# 1-Schematic_light_panel.net
KiCad netlist of a schematic drawn in EasyEDA
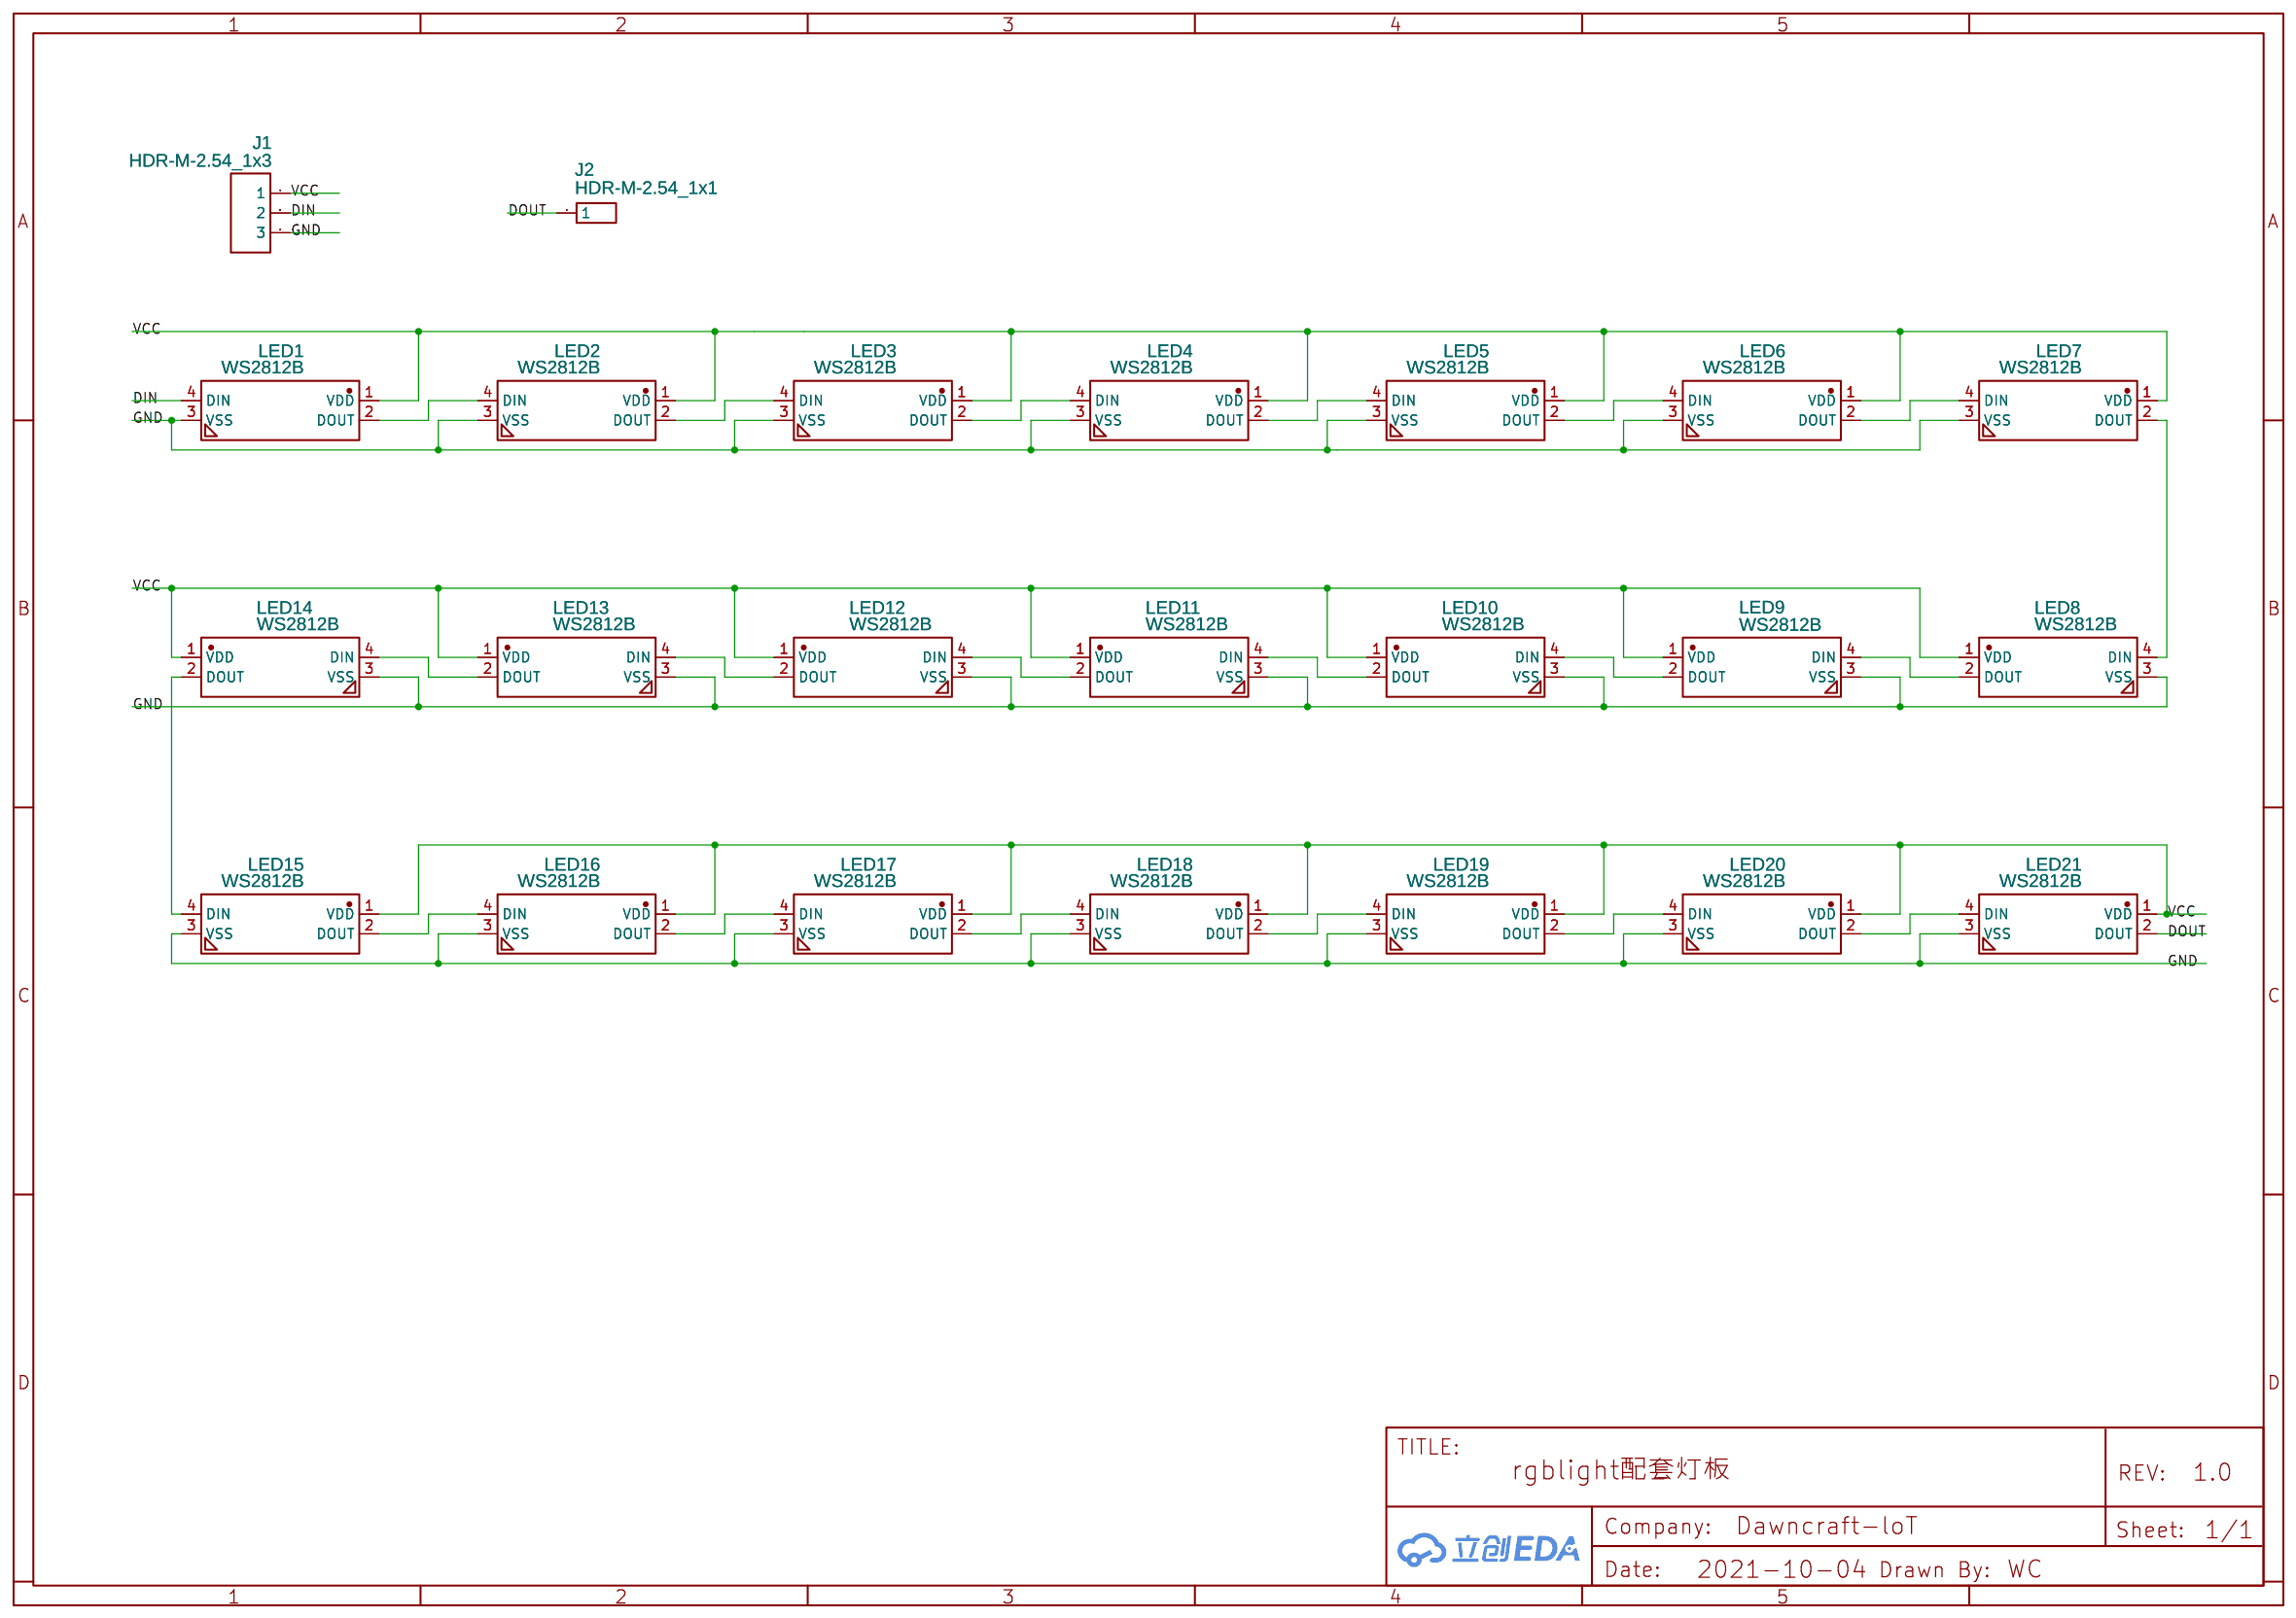
[diagram p0: schematic sheet]

(export (version "E")
  (design (tool "Eeschema 10.0.6"))
  (components
    (comp (ref "J1")
      (value "HDR-M-2.54_1x3")
      (fields (field (name "BOM_Supplier Part") "C180248"))
      (libsource (lib "") (part "HDR-M-2.54_1x3"))
    )
    (comp (ref "J2")
      (value "HDR-M-2.54_1x1")
      (fields (field (name "BOM_Supplier Part") "C81276"))
      (libsource (lib "") (part "HDR-M-2.54_1x1"))
    )
    (comp (ref "LED1")
      (value "WS2812B")
      (fields (field (name "BOM_Supplier Part") "C114585"))
      (libsource (lib "") (part "WS2812B"))
    )
    (comp (ref "LED2")
      (value "WS2812B")
      (fields (field (name "BOM_Supplier Part") "C114585"))
      (libsource (lib "") (part "WS2812B"))
    )
    (comp (ref "LED3")
      (value "WS2812B")
      (fields (field (name "BOM_Supplier Part") "C114585"))
      (libsource (lib "") (part "WS2812B"))
    )
    (comp (ref "LED4")
      (value "WS2812B")
      (fields (field (name "BOM_Supplier Part") "C114585"))
      (libsource (lib "") (part "WS2812B"))
    )
    (comp (ref "LED5")
      (value "WS2812B")
      (fields (field (name "BOM_Supplier Part") "C114585"))
      (libsource (lib "") (part "WS2812B"))
    )
    (comp (ref "LED6")
      (value "WS2812B")
      (fields (field (name "BOM_Supplier Part") "C114585"))
      (libsource (lib "") (part "WS2812B"))
    )
    (comp (ref "LED7")
      (value "WS2812B")
      (fields (field (name "BOM_Supplier Part") "C114585"))
      (libsource (lib "") (part "WS2812B"))
    )
    (comp (ref "LED8")
      (value "WS2812B")
      (fields (field (name "BOM_Supplier Part") "C114585"))
      (libsource (lib "") (part "WS2812B_1"))
    )
    (comp (ref "LED9")
      (value "WS2812B")
      (fields (field (name "BOM_Supplier Part") "C114585"))
      (libsource (lib "") (part "WS2812B_1"))
    )
    (comp (ref "LED10")
      (value "WS2812B")
      (fields (field (name "BOM_Supplier Part") "C114585"))
      (libsource (lib "") (part "WS2812B_1"))
    )
    (comp (ref "LED11")
      (value "WS2812B")
      (fields (field (name "BOM_Supplier Part") "C114585"))
      (libsource (lib "") (part "WS2812B_1"))
    )
    (comp (ref "LED12")
      (value "WS2812B")
      (fields (field (name "BOM_Supplier Part") "C114585"))
      (libsource (lib "") (part "WS2812B_1"))
    )
    (comp (ref "LED13")
      (value "WS2812B")
      (fields (field (name "BOM_Supplier Part") "C114585"))
      (libsource (lib "") (part "WS2812B_1"))
    )
    (comp (ref "LED14")
      (value "WS2812B")
      (fields (field (name "BOM_Supplier Part") "C114585"))
      (libsource (lib "") (part "WS2812B_1"))
    )
    (comp (ref "LED15")
      (value "WS2812B")
      (fields (field (name "BOM_Supplier Part") "C114585"))
      (libsource (lib "") (part "WS2812B"))
    )
    (comp (ref "LED16")
      (value "WS2812B")
      (fields (field (name "BOM_Supplier Part") "C114585"))
      (libsource (lib "") (part "WS2812B"))
    )
    (comp (ref "LED17")
      (value "WS2812B")
      (fields (field (name "BOM_Supplier Part") "C114585"))
      (libsource (lib "") (part "WS2812B"))
    )
    (comp (ref "LED18")
      (value "WS2812B")
      (fields (field (name "BOM_Supplier Part") "C114585"))
      (libsource (lib "") (part "WS2812B"))
    )
    (comp (ref "LED19")
      (value "WS2812B")
      (fields (field (name "BOM_Supplier Part") "C114585"))
      (libsource (lib "") (part "WS2812B"))
    )
    (comp (ref "LED20")
      (value "WS2812B")
      (fields (field (name "BOM_Supplier Part") "C114585"))
      (libsource (lib "") (part "WS2812B"))
    )
    (comp (ref "LED21")
      (value "WS2812B")
      (fields (field (name "BOM_Supplier Part") "C114585"))
      (libsource (lib "") (part "WS2812B"))
    )
  )
  (nets
    (net (code "1") (name "/DIN") (class "Default")
      (node (ref "J1") (pin "2") (pinfunction "2_2") (pintype "input"))
      (node (ref "LED1") (pin "4") (pinfunction "DIN_4") (pintype "unspecified"))
    )
    (net (code "2") (name "/DOUT") (class "Default")
      (node (ref "J2") (pin "1") (pinfunction "1_1") (pintype "input"))
      (node (ref "LED21") (pin "2") (pinfunction "DOUT_2") (pintype "unspecified"))
    )
    (net (code "3") (name "/GND") (class "Default")
      (node (ref "J1") (pin "3") (pinfunction "3_3") (pintype "input"))
      (node (ref "LED1") (pin "3") (pinfunction "VSS_3") (pintype "unspecified"))
      (node (ref "LED10") (pin "3") (pinfunction "VSS_3") (pintype "unspecified"))
      (node (ref "LED11") (pin "3") (pinfunction "VSS_3") (pintype "unspecified"))
      (node (ref "LED12") (pin "3") (pinfunction "VSS_3") (pintype "unspecified"))
      (node (ref "LED13") (pin "3") (pinfunction "VSS_3") (pintype "unspecified"))
      (node (ref "LED14") (pin "3") (pinfunction "VSS_3") (pintype "unspecified"))
      (node (ref "LED15") (pin "3") (pinfunction "VSS_3") (pintype "unspecified"))
      (node (ref "LED16") (pin "3") (pinfunction "VSS_3") (pintype "unspecified"))
      (node (ref "LED17") (pin "3") (pinfunction "VSS_3") (pintype "unspecified"))
      (node (ref "LED18") (pin "3") (pinfunction "VSS_3") (pintype "unspecified"))
      (node (ref "LED19") (pin "3") (pinfunction "VSS_3") (pintype "unspecified"))
      (node (ref "LED2") (pin "3") (pinfunction "VSS_3") (pintype "unspecified"))
      (node (ref "LED20") (pin "3") (pinfunction "VSS_3") (pintype "unspecified"))
      (node (ref "LED21") (pin "3") (pinfunction "VSS_3") (pintype "unspecified"))
      (node (ref "LED3") (pin "3") (pinfunction "VSS_3") (pintype "unspecified"))
      (node (ref "LED4") (pin "3") (pinfunction "VSS_3") (pintype "unspecified"))
      (node (ref "LED5") (pin "3") (pinfunction "VSS_3") (pintype "unspecified"))
      (node (ref "LED6") (pin "3") (pinfunction "VSS_3") (pintype "unspecified"))
      (node (ref "LED7") (pin "3") (pinfunction "VSS_3") (pintype "unspecified"))
      (node (ref "LED8") (pin "3") (pinfunction "VSS_3") (pintype "unspecified"))
      (node (ref "LED9") (pin "3") (pinfunction "VSS_3") (pintype "unspecified"))
    )
    (net (code "4") (name "/VCC") (class "Default")
      (node (ref "J1") (pin "1") (pinfunction "1_1") (pintype "input"))
      (node (ref "LED1") (pin "1") (pinfunction "VDD_1") (pintype "unspecified"))
      (node (ref "LED10") (pin "1") (pinfunction "VDD_1") (pintype "unspecified"))
      (node (ref "LED11") (pin "1") (pinfunction "VDD_1") (pintype "unspecified"))
      (node (ref "LED12") (pin "1") (pinfunction "VDD_1") (pintype "unspecified"))
      (node (ref "LED13") (pin "1") (pinfunction "VDD_1") (pintype "unspecified"))
      (node (ref "LED14") (pin "1") (pinfunction "VDD_1") (pintype "unspecified"))
      (node (ref "LED15") (pin "1") (pinfunction "VDD_1") (pintype "unspecified"))
      (node (ref "LED16") (pin "1") (pinfunction "VDD_1") (pintype "unspecified"))
      (node (ref "LED17") (pin "1") (pinfunction "VDD_1") (pintype "unspecified"))
      (node (ref "LED18") (pin "1") (pinfunction "VDD_1") (pintype "unspecified"))
      (node (ref "LED19") (pin "1") (pinfunction "VDD_1") (pintype "unspecified"))
      (node (ref "LED2") (pin "1") (pinfunction "VDD_1") (pintype "unspecified"))
      (node (ref "LED20") (pin "1") (pinfunction "VDD_1") (pintype "unspecified"))
      (node (ref "LED21") (pin "1") (pinfunction "VDD_1") (pintype "unspecified"))
      (node (ref "LED3") (pin "1") (pinfunction "VDD_1") (pintype "unspecified"))
      (node (ref "LED4") (pin "1") (pinfunction "VDD_1") (pintype "unspecified"))
      (node (ref "LED5") (pin "1") (pinfunction "VDD_1") (pintype "unspecified"))
      (node (ref "LED6") (pin "1") (pinfunction "VDD_1") (pintype "unspecified"))
      (node (ref "LED7") (pin "1") (pinfunction "VDD_1") (pintype "unspecified"))
      (node (ref "LED8") (pin "1") (pinfunction "VDD_1") (pintype "unspecified"))
      (node (ref "LED9") (pin "1") (pinfunction "VDD_1") (pintype "unspecified"))
    )
    (net (code "5") (name "Net-(LED1-DOUT)") (class "Default")
      (node (ref "LED1") (pin "2") (pinfunction "DOUT_2") (pintype "unspecified"))
      (node (ref "LED2") (pin "4") (pinfunction "DIN_4") (pintype "unspecified"))
    )
    (net (code "6") (name "Net-(LED2-DOUT)") (class "Default")
      (node (ref "LED2") (pin "2") (pinfunction "DOUT_2") (pintype "unspecified"))
      (node (ref "LED3") (pin "4") (pinfunction "DIN_4") (pintype "unspecified"))
    )
    (net (code "7") (name "Net-(LED3-DOUT)") (class "Default")
      (node (ref "LED3") (pin "2") (pinfunction "DOUT_2") (pintype "unspecified"))
      (node (ref "LED4") (pin "4") (pinfunction "DIN_4") (pintype "unspecified"))
    )
    (net (code "8") (name "Net-(LED4-DOUT)") (class "Default")
      (node (ref "LED4") (pin "2") (pinfunction "DOUT_2") (pintype "unspecified"))
      (node (ref "LED5") (pin "4") (pinfunction "DIN_4") (pintype "unspecified"))
    )
    (net (code "9") (name "Net-(LED5-DOUT)") (class "Default")
      (node (ref "LED5") (pin "2") (pinfunction "DOUT_2") (pintype "unspecified"))
      (node (ref "LED6") (pin "4") (pinfunction "DIN_4") (pintype "unspecified"))
    )
    (net (code "10") (name "Net-(LED6-DOUT)") (class "Default")
      (node (ref "LED6") (pin "2") (pinfunction "DOUT_2") (pintype "unspecified"))
      (node (ref "LED7") (pin "4") (pinfunction "DIN_4") (pintype "unspecified"))
    )
    (net (code "11") (name "Net-(LED7-DOUT)") (class "Default")
      (node (ref "LED7") (pin "2") (pinfunction "DOUT_2") (pintype "unspecified"))
      (node (ref "LED8") (pin "4") (pinfunction "DIN_4") (pintype "unspecified"))
    )
    (net (code "12") (name "Net-(LED8-DOUT)") (class "Default")
      (node (ref "LED8") (pin "2") (pinfunction "DOUT_2") (pintype "unspecified"))
      (node (ref "LED9") (pin "4") (pinfunction "DIN_4") (pintype "unspecified"))
    )
    (net (code "13") (name "Net-(LED10-DIN)") (class "Default")
      (node (ref "LED10") (pin "4") (pinfunction "DIN_4") (pintype "unspecified"))
      (node (ref "LED9") (pin "2") (pinfunction "DOUT_2") (pintype "unspecified"))
    )
    (net (code "14") (name "Net-(LED10-DOUT)") (class "Default")
      (node (ref "LED10") (pin "2") (pinfunction "DOUT_2") (pintype "unspecified"))
      (node (ref "LED11") (pin "4") (pinfunction "DIN_4") (pintype "unspecified"))
    )
    (net (code "15") (name "Net-(LED11-DOUT)") (class "Default")
      (node (ref "LED11") (pin "2") (pinfunction "DOUT_2") (pintype "unspecified"))
      (node (ref "LED12") (pin "4") (pinfunction "DIN_4") (pintype "unspecified"))
    )
    (net (code "16") (name "Net-(LED12-DOUT)") (class "Default")
      (node (ref "LED12") (pin "2") (pinfunction "DOUT_2") (pintype "unspecified"))
      (node (ref "LED13") (pin "4") (pinfunction "DIN_4") (pintype "unspecified"))
    )
    (net (code "17") (name "Net-(LED13-DOUT)") (class "Default")
      (node (ref "LED13") (pin "2") (pinfunction "DOUT_2") (pintype "unspecified"))
      (node (ref "LED14") (pin "4") (pinfunction "DIN_4") (pintype "unspecified"))
    )
    (net (code "18") (name "Net-(LED14-DOUT)") (class "Default")
      (node (ref "LED14") (pin "2") (pinfunction "DOUT_2") (pintype "unspecified"))
      (node (ref "LED15") (pin "4") (pinfunction "DIN_4") (pintype "unspecified"))
    )
    (net (code "19") (name "Net-(LED15-DOUT)") (class "Default")
      (node (ref "LED15") (pin "2") (pinfunction "DOUT_2") (pintype "unspecified"))
      (node (ref "LED16") (pin "4") (pinfunction "DIN_4") (pintype "unspecified"))
    )
    (net (code "20") (name "Net-(LED16-DOUT)") (class "Default")
      (node (ref "LED16") (pin "2") (pinfunction "DOUT_2") (pintype "unspecified"))
      (node (ref "LED17") (pin "4") (pinfunction "DIN_4") (pintype "unspecified"))
    )
    (net (code "21") (name "Net-(LED17-DOUT)") (class "Default")
      (node (ref "LED17") (pin "2") (pinfunction "DOUT_2") (pintype "unspecified"))
      (node (ref "LED18") (pin "4") (pinfunction "DIN_4") (pintype "unspecified"))
    )
    (net (code "22") (name "Net-(LED18-DOUT)") (class "Default")
      (node (ref "LED18") (pin "2") (pinfunction "DOUT_2") (pintype "unspecified"))
      (node (ref "LED19") (pin "4") (pinfunction "DIN_4") (pintype "unspecified"))
    )
    (net (code "23") (name "Net-(LED19-DOUT)") (class "Default")
      (node (ref "LED19") (pin "2") (pinfunction "DOUT_2") (pintype "unspecified"))
      (node (ref "LED20") (pin "4") (pinfunction "DIN_4") (pintype "unspecified"))
    )
    (net (code "24") (name "Net-(LED20-DOUT)") (class "Default")
      (node (ref "LED20") (pin "2") (pinfunction "DOUT_2") (pintype "unspecified"))
      (node (ref "LED21") (pin "4") (pinfunction "DIN_4") (pintype "unspecified"))
    )
  )
)
